# atum-breakout.net
KiCad netlist of a schematic drawn in EAGLE
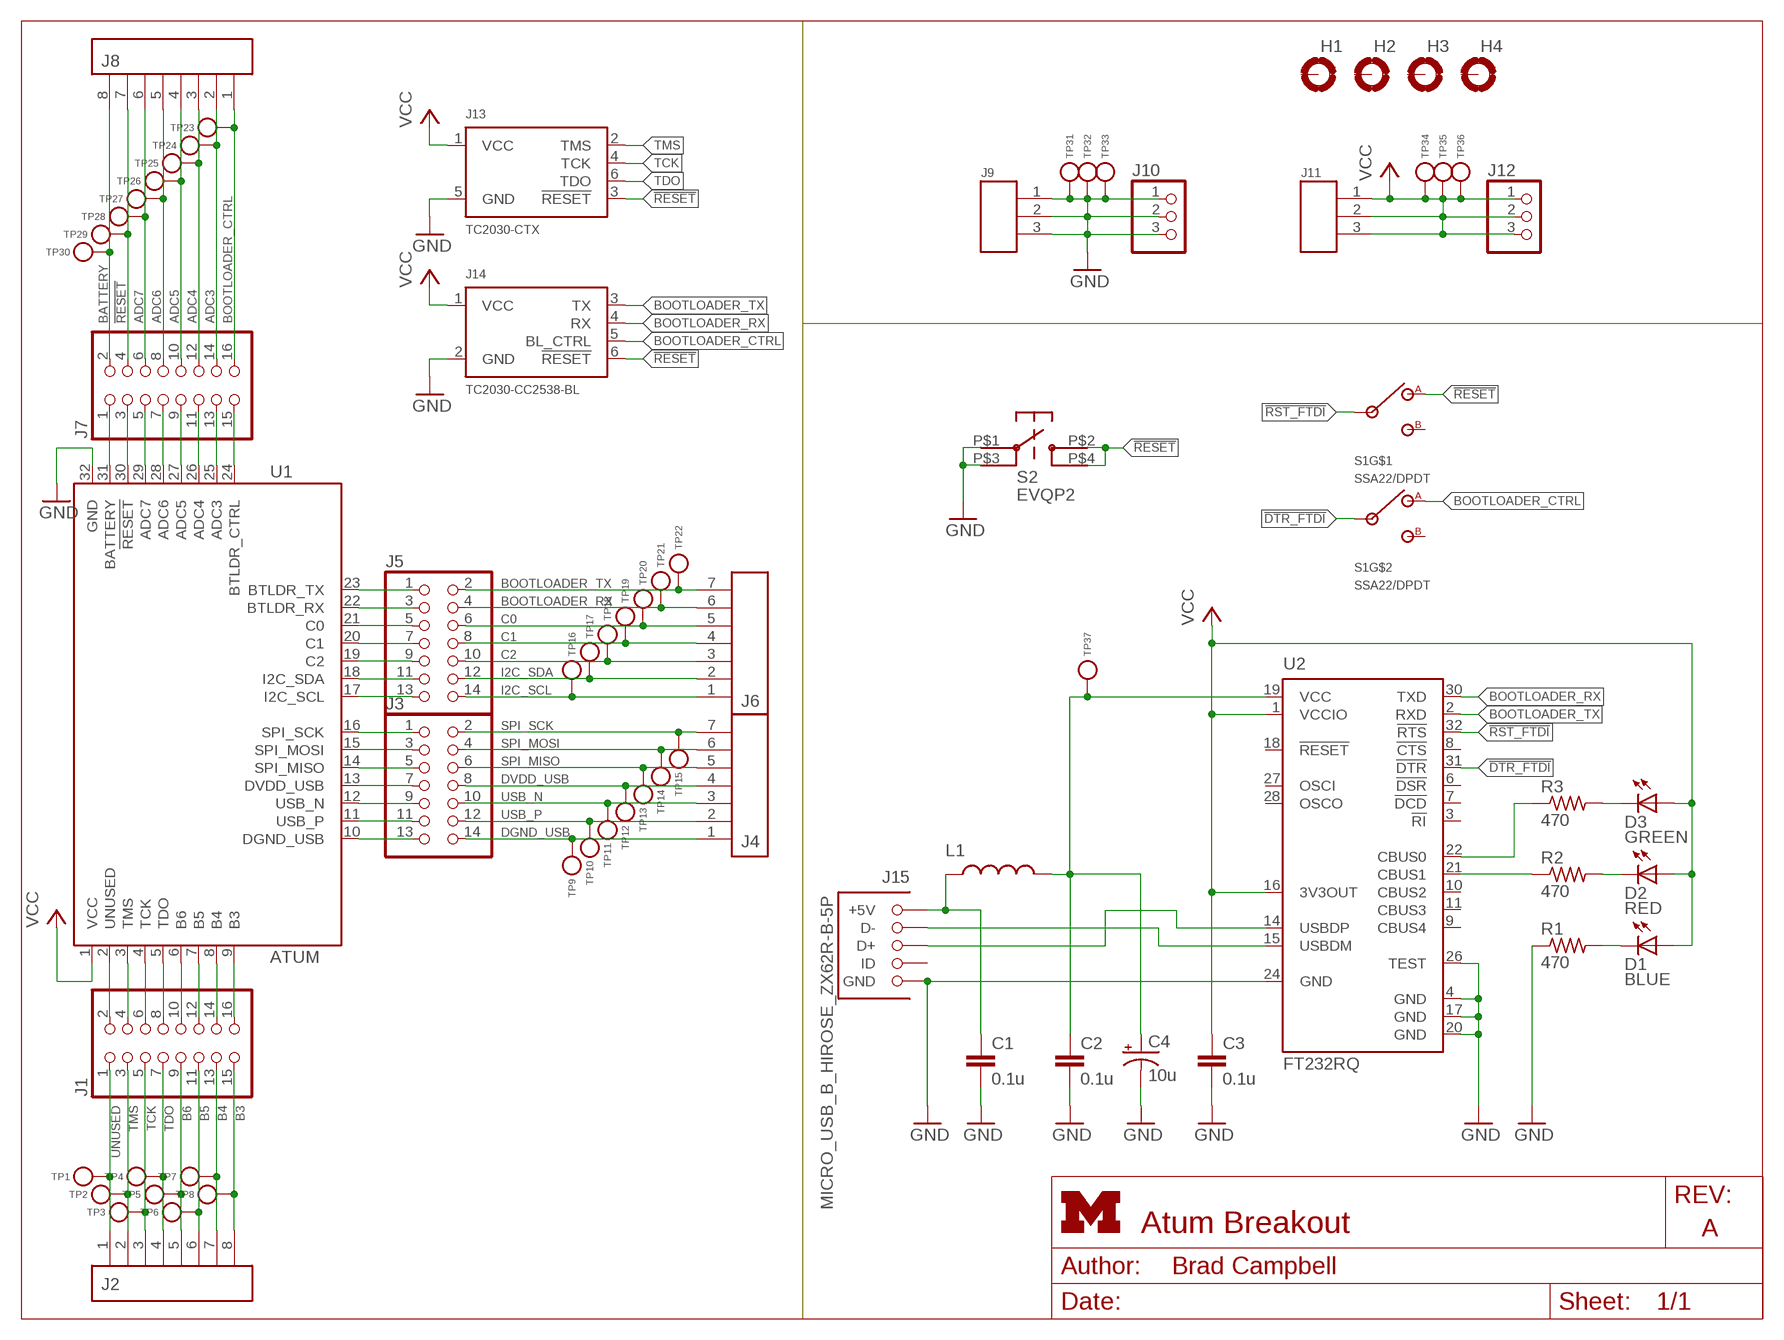
[diagram p0: schematic, sheet 1]

(export (version "E")
  (design (tool "Eeschema 10.0.6"))
  (components
    (comp (ref "C1")
      (value "0.1u")
      (footprint "eagle-import:C0603")
      (libsource (lib "eagle-import") (part "C-EUC0603"))
    )
    (comp (ref "C2")
      (value "0.1u")
      (footprint "eagle-import:C0603")
      (libsource (lib "eagle-import") (part "C-EUC0603"))
    )
    (comp (ref "C3")
      (value "0.1u")
      (footprint "eagle-import:C0603")
      (libsource (lib "eagle-import") (part "C-EUC0603"))
    )
    (comp (ref "C4")
      (value "10u")
      (footprint "eagle-import:EIA3216")
      (libsource (lib "eagle-import") (part "CAP_POL1206"))
    )
    (comp (ref "D1")
      (value "BLUE")
      (footprint "eagle-import:LED-0603")
      (libsource (lib "eagle-import") (part "LED0603"))
    )
    (comp (ref "D2")
      (value "RED")
      (footprint "eagle-import:LED-0603")
      (libsource (lib "eagle-import") (part "LED0603"))
    )
    (comp (ref "D3")
      (value "GREEN")
      (footprint "eagle-import:LED-0603")
      (libsource (lib "eagle-import") (part "LED0603"))
    )
    (comp (ref "H1")
      (value "MOUNT-PAD-ROUND3.2")
      (footprint "eagle-import:3,2-PAD")
      (libsource (lib "eagle-import") (part "MOUNT-PAD-ROUND3.2"))
    )
    (comp (ref "H2")
      (value "MOUNT-PAD-ROUND3.2")
      (footprint "eagle-import:3,2-PAD")
      (libsource (lib "eagle-import") (part "MOUNT-PAD-ROUND3.2"))
    )
    (comp (ref "H3")
      (value "MOUNT-PAD-ROUND3.2")
      (footprint "eagle-import:3,2-PAD")
      (libsource (lib "eagle-import") (part "MOUNT-PAD-ROUND3.2"))
    )
    (comp (ref "H4")
      (value "MOUNT-PAD-ROUND3.2")
      (footprint "eagle-import:3,2-PAD")
      (libsource (lib "eagle-import") (part "MOUNT-PAD-ROUND3.2"))
    )
    (comp (ref "J1")
      (value "PINHD-2X8")
      (footprint "eagle-import:2X08")
      (libsource (lib "eagle-import") (part "PINHD-2X8"))
    )
    (comp (ref "J2")
      (value "SCREW-TERMINAL_8_0.100")
      (footprint "eagle-import:CONN_BLOCK_8")
      (libsource (lib "eagle-import") (part "SCREW-TERMINAL_8_0.100"))
    )
    (comp (ref "J3")
      (value "PINHD-2X7")
      (footprint "eagle-import:2X07")
      (libsource (lib "eagle-import") (part "PINHD-2X7"))
    )
    (comp (ref "J4")
      (value "SCREW-TERMINAL_7_0.100")
      (footprint "eagle-import:CONN_BLOCK_7")
      (libsource (lib "eagle-import") (part "SCREW-TERMINAL_7_0.100"))
    )
    (comp (ref "J5")
      (value "PINHD-2X7")
      (footprint "eagle-import:2X07")
      (libsource (lib "eagle-import") (part "PINHD-2X7"))
    )
    (comp (ref "J6")
      (value "SCREW-TERMINAL_7_0.100")
      (footprint "eagle-import:CONN_BLOCK_7")
      (libsource (lib "eagle-import") (part "SCREW-TERMINAL_7_0.100"))
    )
    (comp (ref "J7")
      (value "PINHD-2X8")
      (footprint "eagle-import:2X08")
      (libsource (lib "eagle-import") (part "PINHD-2X8"))
    )
    (comp (ref "J8")
      (value "SCREW-TERMINAL_8_0.100")
      (footprint "eagle-import:CONN_BLOCK_8")
      (libsource (lib "eagle-import") (part "SCREW-TERMINAL_8_0.100"))
    )
    (comp (ref "J9")
      (value "SCREW-TERMINAL_3_0.100")
      (footprint "eagle-import:CONN_BLOCK_3")
      (libsource (lib "eagle-import") (part "SCREW-TERMINAL_3_0.100"))
    )
    (comp (ref "J10")
      (value "PINHD-1X3")
      (footprint "eagle-import:1X03")
      (libsource (lib "eagle-import") (part "PINHD-1X3"))
    )
    (comp (ref "J11")
      (value "SCREW-TERMINAL_3_0.100")
      (footprint "eagle-import:CONN_BLOCK_3")
      (libsource (lib "eagle-import") (part "SCREW-TERMINAL_3_0.100"))
    )
    (comp (ref "J12")
      (value "PINHD-1X3")
      (footprint "eagle-import:1X03")
      (libsource (lib "eagle-import") (part "PINHD-1X3"))
    )
    (comp (ref "J13")
      (value "TC2030-CTX")
      (footprint "eagle-import:TC2030-IDC")
      (libsource (lib "eagle-import") (part "TC2030-CTX"))
    )
    (comp (ref "J14")
      (value "TC2030-CC2538-BL")
      (footprint "eagle-import:TC2030-IDC")
      (libsource (lib "eagle-import") (part "TC2030-CC2538-BL"))
    )
    (comp (ref "J15")
      (value "MICRO_USB_B_HIROSE_ZX62R-B-5P")
      (footprint "eagle-import:USB_MICRO_B-HIROSE-ZX62R-B-5P")
      (libsource (lib "eagle-import") (part "MICRO_USB_B_HIROSE_ZX62R-B-5P"))
    )
    (comp (ref "L1")
      (value "INDUCTOR0603")
      (footprint "eagle-import:0603")
      (libsource (lib "eagle-import") (part "INDUCTOR0603"))
    )
    (comp (ref "R1")
      (value "470")
      (footprint "eagle-import:R0603")
      (libsource (lib "eagle-import") (part "R-US_R0603"))
    )
    (comp (ref "R2")
      (value "470")
      (footprint "eagle-import:R0603")
      (libsource (lib "eagle-import") (part "R-US_R0603"))
    )
    (comp (ref "R3")
      (value "470")
      (footprint "eagle-import:R0603")
      (libsource (lib "eagle-import") (part "R-US_R0603"))
    )
    (comp (ref "S1")
      (value "SSA22/DPDT")
      (footprint "eagle-import:SSA22_DPDT")
      (fields
        (field (name "DIGIKEY") "450-1604-ND")
        (field (name "MOUSER") "506-SSA22")
        (field (name "NEWARK") "50F5561")
      )
      (libsource (lib "eagle-import") (part "SSA22/DPDT"))
    )
    (comp (ref "S2")
      (value "EVQP2")
      (footprint "eagle-import:EVQP2")
      (libsource (lib "eagle-import") (part "EVQP2"))
    )
    (comp (ref "TP1")
      (value "TEST_POINT_0.040IN")
      (footprint "eagle-import:TESTPOINT_0.040IN")
      (libsource (lib "eagle-import") (part "TEST_POINT_0.040IN"))
    )
    (comp (ref "TP2")
      (value "TEST_POINT_0.040IN")
      (footprint "eagle-import:TESTPOINT_0.040IN")
      (libsource (lib "eagle-import") (part "TEST_POINT_0.040IN"))
    )
    (comp (ref "TP3")
      (value "TEST_POINT_0.040IN")
      (footprint "eagle-import:TESTPOINT_0.040IN")
      (libsource (lib "eagle-import") (part "TEST_POINT_0.040IN"))
    )
    (comp (ref "TP4")
      (value "TEST_POINT_0.040IN")
      (footprint "eagle-import:TESTPOINT_0.040IN")
      (libsource (lib "eagle-import") (part "TEST_POINT_0.040IN"))
    )
    (comp (ref "TP5")
      (value "TEST_POINT_0.040IN")
      (footprint "eagle-import:TESTPOINT_0.040IN")
      (libsource (lib "eagle-import") (part "TEST_POINT_0.040IN"))
    )
    (comp (ref "TP6")
      (value "TEST_POINT_0.040IN")
      (footprint "eagle-import:TESTPOINT_0.040IN")
      (libsource (lib "eagle-import") (part "TEST_POINT_0.040IN"))
    )
    (comp (ref "TP7")
      (value "TEST_POINT_0.040IN")
      (footprint "eagle-import:TESTPOINT_0.040IN")
      (libsource (lib "eagle-import") (part "TEST_POINT_0.040IN"))
    )
    (comp (ref "TP8")
      (value "TEST_POINT_0.040IN")
      (footprint "eagle-import:TESTPOINT_0.040IN")
      (libsource (lib "eagle-import") (part "TEST_POINT_0.040IN"))
    )
    (comp (ref "TP9")
      (value "TEST_POINT_0.040IN")
      (footprint "eagle-import:TESTPOINT_0.040IN")
      (libsource (lib "eagle-import") (part "TEST_POINT_0.040IN"))
    )
    (comp (ref "TP10")
      (value "TEST_POINT_0.040IN")
      (footprint "eagle-import:TESTPOINT_0.040IN")
      (libsource (lib "eagle-import") (part "TEST_POINT_0.040IN"))
    )
    (comp (ref "TP11")
      (value "TEST_POINT_0.040IN")
      (footprint "eagle-import:TESTPOINT_0.040IN")
      (libsource (lib "eagle-import") (part "TEST_POINT_0.040IN"))
    )
    (comp (ref "TP12")
      (value "TEST_POINT_0.040IN")
      (footprint "eagle-import:TESTPOINT_0.040IN")
      (libsource (lib "eagle-import") (part "TEST_POINT_0.040IN"))
    )
    (comp (ref "TP13")
      (value "TEST_POINT_0.040IN")
      (footprint "eagle-import:TESTPOINT_0.040IN")
      (libsource (lib "eagle-import") (part "TEST_POINT_0.040IN"))
    )
    (comp (ref "TP14")
      (value "TEST_POINT_0.040IN")
      (footprint "eagle-import:TESTPOINT_0.040IN")
      (libsource (lib "eagle-import") (part "TEST_POINT_0.040IN"))
    )
    (comp (ref "TP15")
      (value "TEST_POINT_0.040IN")
      (footprint "eagle-import:TESTPOINT_0.040IN")
      (libsource (lib "eagle-import") (part "TEST_POINT_0.040IN"))
    )
    (comp (ref "TP16")
      (value "TEST_POINT_0.040IN")
      (footprint "eagle-import:TESTPOINT_0.040IN")
      (libsource (lib "eagle-import") (part "TEST_POINT_0.040IN"))
    )
    (comp (ref "TP17")
      (value "TEST_POINT_0.040IN")
      (footprint "eagle-import:TESTPOINT_0.040IN")
      (libsource (lib "eagle-import") (part "TEST_POINT_0.040IN"))
    )
    (comp (ref "TP18")
      (value "TEST_POINT_0.040IN")
      (footprint "eagle-import:TESTPOINT_0.040IN")
      (libsource (lib "eagle-import") (part "TEST_POINT_0.040IN"))
    )
    (comp (ref "TP19")
      (value "TEST_POINT_0.040IN")
      (footprint "eagle-import:TESTPOINT_0.040IN")
      (libsource (lib "eagle-import") (part "TEST_POINT_0.040IN"))
    )
    (comp (ref "TP20")
      (value "TEST_POINT_0.040IN")
      (footprint "eagle-import:TESTPOINT_0.040IN")
      (libsource (lib "eagle-import") (part "TEST_POINT_0.040IN"))
    )
    (comp (ref "TP21")
      (value "TEST_POINT_0.040IN")
      (footprint "eagle-import:TESTPOINT_0.040IN")
      (libsource (lib "eagle-import") (part "TEST_POINT_0.040IN"))
    )
    (comp (ref "TP22")
      (value "TEST_POINT_0.040IN")
      (footprint "eagle-import:TESTPOINT_0.040IN")
      (libsource (lib "eagle-import") (part "TEST_POINT_0.040IN"))
    )
    (comp (ref "TP23")
      (value "TEST_POINT_0.040IN")
      (footprint "eagle-import:TESTPOINT_0.040IN")
      (libsource (lib "eagle-import") (part "TEST_POINT_0.040IN"))
    )
    (comp (ref "TP24")
      (value "TEST_POINT_0.040IN")
      (footprint "eagle-import:TESTPOINT_0.040IN")
      (libsource (lib "eagle-import") (part "TEST_POINT_0.040IN"))
    )
    (comp (ref "TP25")
      (value "TEST_POINT_0.040IN")
      (footprint "eagle-import:TESTPOINT_0.040IN")
      (libsource (lib "eagle-import") (part "TEST_POINT_0.040IN"))
    )
    (comp (ref "TP26")
      (value "TEST_POINT_0.040IN")
      (footprint "eagle-import:TESTPOINT_0.040IN")
      (libsource (lib "eagle-import") (part "TEST_POINT_0.040IN"))
    )
    (comp (ref "TP27")
      (value "TEST_POINT_0.040IN")
      (footprint "eagle-import:TESTPOINT_0.040IN")
      (libsource (lib "eagle-import") (part "TEST_POINT_0.040IN"))
    )
    (comp (ref "TP28")
      (value "TEST_POINT_0.040IN")
      (footprint "eagle-import:TESTPOINT_0.040IN")
      (libsource (lib "eagle-import") (part "TEST_POINT_0.040IN"))
    )
    (comp (ref "TP29")
      (value "TEST_POINT_0.040IN")
      (footprint "eagle-import:TESTPOINT_0.040IN")
      (libsource (lib "eagle-import") (part "TEST_POINT_0.040IN"))
    )
    (comp (ref "TP30")
      (value "TEST_POINT_0.040IN")
      (footprint "eagle-import:TESTPOINT_0.040IN")
      (libsource (lib "eagle-import") (part "TEST_POINT_0.040IN"))
    )
    (comp (ref "TP31")
      (value "TEST_POINT_0.040IN")
      (footprint "eagle-import:TESTPOINT_0.040IN")
      (libsource (lib "eagle-import") (part "TEST_POINT_0.040IN"))
    )
    (comp (ref "TP32")
      (value "TEST_POINT_0.040IN")
      (footprint "eagle-import:TESTPOINT_0.040IN")
      (libsource (lib "eagle-import") (part "TEST_POINT_0.040IN"))
    )
    (comp (ref "TP33")
      (value "TEST_POINT_0.040IN")
      (footprint "eagle-import:TESTPOINT_0.040IN")
      (libsource (lib "eagle-import") (part "TEST_POINT_0.040IN"))
    )
    (comp (ref "TP34")
      (value "TEST_POINT_0.040IN")
      (footprint "eagle-import:TESTPOINT_0.040IN")
      (libsource (lib "eagle-import") (part "TEST_POINT_0.040IN"))
    )
    (comp (ref "TP35")
      (value "TEST_POINT_0.040IN")
      (footprint "eagle-import:TESTPOINT_0.040IN")
      (libsource (lib "eagle-import") (part "TEST_POINT_0.040IN"))
    )
    (comp (ref "TP36")
      (value "TEST_POINT_0.040IN")
      (footprint "eagle-import:TESTPOINT_0.040IN")
      (libsource (lib "eagle-import") (part "TEST_POINT_0.040IN"))
    )
    (comp (ref "TP37")
      (value "TEST_POINT_0.040IN")
      (footprint "eagle-import:TESTPOINT_0.040IN")
      (libsource (lib "eagle-import") (part "TEST_POINT_0.040IN"))
    )
    (comp (ref "U1")
      (value "ATUM")
      (footprint "eagle-import:ATUM")
      (libsource (lib "eagle-import") (part "ATUM"))
    )
    (comp (ref "U2")
      (value "FT232RQ")
      (footprint "eagle-import:QFN32")
      (libsource (lib "eagle-import") (part "FT232RQ"))
    )
  )
  (nets
    (net (code "1") (name "/ADC3") (class "Default")
      (node (ref "J7") (pin "13") (pinfunction "13_13") (pintype "passive"))
      (node (ref "J7") (pin "14") (pinfunction "14_14") (pintype "passive"))
      (node (ref "J8") (pin "2") (pinfunction "2_2") (pintype "bidirectional"))
      (node (ref "TP24") (pin "TESTPOINT") (pinfunction "TESTPOINT_TESTPOINT") (pintype "bidirectional"))
      (node (ref "U1") (pin "25") (pinfunction "ADC3_25") (pintype "bidirectional"))
    )
    (net (code "2") (name "/ADC4") (class "Default")
      (node (ref "J7") (pin "11") (pinfunction "11_11") (pintype "passive"))
      (node (ref "J7") (pin "12") (pinfunction "12_12") (pintype "passive"))
      (node (ref "J8") (pin "3") (pinfunction "3_3") (pintype "bidirectional"))
      (node (ref "TP25") (pin "TESTPOINT") (pinfunction "TESTPOINT_TESTPOINT") (pintype "bidirectional"))
      (node (ref "U1") (pin "26") (pinfunction "ADC4_26") (pintype "bidirectional"))
    )
    (net (code "3") (name "/ADC5") (class "Default")
      (node (ref "J7") (pin "10") (pinfunction "10_10") (pintype "passive"))
      (node (ref "J7") (pin "9") (pinfunction "9_9") (pintype "passive"))
      (node (ref "J8") (pin "4") (pinfunction "4_4") (pintype "bidirectional"))
      (node (ref "TP26") (pin "TESTPOINT") (pinfunction "TESTPOINT_TESTPOINT") (pintype "bidirectional"))
      (node (ref "U1") (pin "27") (pinfunction "ADC5_27") (pintype "bidirectional"))
    )
    (net (code "4") (name "/ADC6") (class "Default")
      (node (ref "J7") (pin "7") (pinfunction "7_7") (pintype "passive"))
      (node (ref "J7") (pin "8") (pinfunction "8_8") (pintype "passive"))
      (node (ref "J8") (pin "5") (pinfunction "5_5") (pintype "bidirectional"))
      (node (ref "TP27") (pin "TESTPOINT") (pinfunction "TESTPOINT_TESTPOINT") (pintype "bidirectional"))
      (node (ref "U1") (pin "28") (pinfunction "ADC6_28") (pintype "bidirectional"))
    )
    (net (code "5") (name "/ADC7") (class "Default")
      (node (ref "J7") (pin "5") (pinfunction "5_5") (pintype "passive"))
      (node (ref "J7") (pin "6") (pinfunction "6_6") (pintype "passive"))
      (node (ref "J8") (pin "6") (pinfunction "6_6") (pintype "bidirectional"))
      (node (ref "TP28") (pin "TESTPOINT") (pinfunction "TESTPOINT_TESTPOINT") (pintype "bidirectional"))
      (node (ref "U1") (pin "29") (pinfunction "ADC7_29") (pintype "bidirectional"))
    )
    (net (code "6") (name "/B3") (class "Default")
      (node (ref "J1") (pin "15") (pinfunction "15_15") (pintype "passive"))
      (node (ref "J1") (pin "16") (pinfunction "16_16") (pintype "passive"))
      (node (ref "J2") (pin "8") (pinfunction "8_8") (pintype "bidirectional"))
      (node (ref "TP8") (pin "TESTPOINT") (pinfunction "TESTPOINT_TESTPOINT") (pintype "bidirectional"))
      (node (ref "U1") (pin "9") (pinfunction "B3_9") (pintype "bidirectional"))
    )
    (net (code "7") (name "/B4") (class "Default")
      (node (ref "J1") (pin "13") (pinfunction "13_13") (pintype "passive"))
      (node (ref "J1") (pin "14") (pinfunction "14_14") (pintype "passive"))
      (node (ref "J2") (pin "7") (pinfunction "7_7") (pintype "bidirectional"))
      (node (ref "TP7") (pin "TESTPOINT") (pinfunction "TESTPOINT_TESTPOINT") (pintype "bidirectional"))
      (node (ref "U1") (pin "8") (pinfunction "B4_8") (pintype "bidirectional"))
    )
    (net (code "8") (name "/B5") (class "Default")
      (node (ref "J1") (pin "11") (pinfunction "11_11") (pintype "passive"))
      (node (ref "J1") (pin "12") (pinfunction "12_12") (pintype "passive"))
      (node (ref "J2") (pin "6") (pinfunction "6_6") (pintype "bidirectional"))
      (node (ref "TP6") (pin "TESTPOINT") (pinfunction "TESTPOINT_TESTPOINT") (pintype "bidirectional"))
      (node (ref "U1") (pin "7") (pinfunction "B5_7") (pintype "bidirectional"))
    )
    (net (code "9") (name "/B6") (class "Default")
      (node (ref "J1") (pin "10") (pinfunction "10_10") (pintype "passive"))
      (node (ref "J1") (pin "9") (pinfunction "9_9") (pintype "passive"))
      (node (ref "J2") (pin "5") (pinfunction "5_5") (pintype "bidirectional"))
      (node (ref "TP5") (pin "TESTPOINT") (pinfunction "TESTPOINT_TESTPOINT") (pintype "bidirectional"))
      (node (ref "U1") (pin "6") (pinfunction "B6_6") (pintype "bidirectional"))
    )
    (net (code "10") (name "/BATTERY") (class "Default")
      (node (ref "J7") (pin "1") (pinfunction "1_1") (pintype "passive"))
      (node (ref "J7") (pin "2") (pinfunction "2_2") (pintype "passive"))
      (node (ref "J8") (pin "8") (pinfunction "8_8") (pintype "bidirectional"))
      (node (ref "TP30") (pin "TESTPOINT") (pinfunction "TESTPOINT_TESTPOINT") (pintype "bidirectional"))
      (node (ref "U1") (pin "31") (pinfunction "BATTERY_31") (pintype "bidirectional"))
    )
    (net (code "11") (name "/C0") (class "Default")
      (node (ref "J5") (pin "5") (pinfunction "5_5") (pintype "passive"))
      (node (ref "J5") (pin "6") (pinfunction "6_6") (pintype "passive"))
      (node (ref "J6") (pin "5") (pinfunction "5_5") (pintype "bidirectional"))
      (node (ref "TP20") (pin "TESTPOINT") (pinfunction "TESTPOINT_TESTPOINT") (pintype "bidirectional"))
      (node (ref "U1") (pin "21") (pinfunction "C0_21") (pintype "bidirectional"))
    )
    (net (code "12") (name "/C1") (class "Default")
      (node (ref "J5") (pin "7") (pinfunction "7_7") (pintype "passive"))
      (node (ref "J5") (pin "8") (pinfunction "8_8") (pintype "passive"))
      (node (ref "J6") (pin "4") (pinfunction "4_4") (pintype "bidirectional"))
      (node (ref "TP19") (pin "TESTPOINT") (pinfunction "TESTPOINT_TESTPOINT") (pintype "bidirectional"))
      (node (ref "U1") (pin "20") (pinfunction "C1_20") (pintype "bidirectional"))
    )
    (net (code "13") (name "/C2") (class "Default")
      (node (ref "J5") (pin "10") (pinfunction "10_10") (pintype "passive"))
      (node (ref "J5") (pin "9") (pinfunction "9_9") (pintype "passive"))
      (node (ref "J6") (pin "3") (pinfunction "3_3") (pintype "bidirectional"))
      (node (ref "TP18") (pin "TESTPOINT") (pinfunction "TESTPOINT_TESTPOINT") (pintype "bidirectional"))
      (node (ref "U1") (pin "19") (pinfunction "C2_19") (pintype "bidirectional"))
    )
    (net (code "14") (name "/DGND_USB") (class "Default")
      (node (ref "J3") (pin "13") (pinfunction "13_13") (pintype "passive"))
      (node (ref "J3") (pin "14") (pinfunction "14_14") (pintype "passive"))
      (node (ref "J4") (pin "1") (pinfunction "1_1") (pintype "bidirectional"))
      (node (ref "TP9") (pin "TESTPOINT") (pinfunction "TESTPOINT_TESTPOINT") (pintype "bidirectional"))
      (node (ref "U1") (pin "10") (pinfunction "DGND_USB_10") (pintype "bidirectional"))
    )
    (net (code "15") (name "/DVDD_USB") (class "Default")
      (node (ref "J3") (pin "7") (pinfunction "7_7") (pintype "passive"))
      (node (ref "J3") (pin "8") (pinfunction "8_8") (pintype "passive"))
      (node (ref "J4") (pin "4") (pinfunction "4_4") (pintype "bidirectional"))
      (node (ref "TP12") (pin "TESTPOINT") (pinfunction "TESTPOINT_TESTPOINT") (pintype "bidirectional"))
      (node (ref "U1") (pin "13") (pinfunction "DVDD_USB_13") (pintype "bidirectional"))
    )
    (net (code "16") (name "/I2C_SCL") (class "Default")
      (node (ref "J5") (pin "13") (pinfunction "13_13") (pintype "passive"))
      (node (ref "J5") (pin "14") (pinfunction "14_14") (pintype "passive"))
      (node (ref "J6") (pin "1") (pinfunction "1_1") (pintype "bidirectional"))
      (node (ref "TP16") (pin "TESTPOINT") (pinfunction "TESTPOINT_TESTPOINT") (pintype "bidirectional"))
      (node (ref "U1") (pin "17") (pinfunction "I2C_SCL_17") (pintype "bidirectional"))
    )
    (net (code "17") (name "/I2C_SDA") (class "Default")
      (node (ref "J5") (pin "11") (pinfunction "11_11") (pintype "passive"))
      (node (ref "J5") (pin "12") (pinfunction "12_12") (pintype "passive"))
      (node (ref "J6") (pin "2") (pinfunction "2_2") (pintype "bidirectional"))
      (node (ref "TP17") (pin "TESTPOINT") (pinfunction "TESTPOINT_TESTPOINT") (pintype "bidirectional"))
      (node (ref "U1") (pin "18") (pinfunction "I2C_SDA_18") (pintype "bidirectional"))
    )
    (net (code "18") (name "/SPI_MISO") (class "Default")
      (node (ref "J3") (pin "5") (pinfunction "5_5") (pintype "passive"))
      (node (ref "J3") (pin "6") (pinfunction "6_6") (pintype "passive"))
      (node (ref "J4") (pin "5") (pinfunction "5_5") (pintype "bidirectional"))
      (node (ref "TP13") (pin "TESTPOINT") (pinfunction "TESTPOINT_TESTPOINT") (pintype "bidirectional"))
      (node (ref "U1") (pin "14") (pinfunction "SPI_MISO_14") (pintype "bidirectional"))
    )
    (net (code "19") (name "/SPI_MOSI") (class "Default")
      (node (ref "J3") (pin "3") (pinfunction "3_3") (pintype "passive"))
      (node (ref "J3") (pin "4") (pinfunction "4_4") (pintype "passive"))
      (node (ref "J4") (pin "6") (pinfunction "6_6") (pintype "bidirectional"))
      (node (ref "TP14") (pin "TESTPOINT") (pinfunction "TESTPOINT_TESTPOINT") (pintype "bidirectional"))
      (node (ref "U1") (pin "15") (pinfunction "SPI_MOSI_15") (pintype "bidirectional"))
    )
    (net (code "20") (name "/SPI_SCK") (class "Default")
      (node (ref "J3") (pin "1") (pinfunction "1_1") (pintype "passive"))
      (node (ref "J3") (pin "2") (pinfunction "2_2") (pintype "passive"))
      (node (ref "J4") (pin "7") (pinfunction "7_7") (pintype "bidirectional"))
      (node (ref "TP15") (pin "TESTPOINT") (pinfunction "TESTPOINT_TESTPOINT") (pintype "bidirectional"))
      (node (ref "U1") (pin "16") (pinfunction "SPI_SCK_16") (pintype "bidirectional"))
    )
    (net (code "21") (name "/UNUSED") (class "Default")
      (node (ref "J1") (pin "1") (pinfunction "1_1") (pintype "passive"))
      (node (ref "J1") (pin "2") (pinfunction "2_2") (pintype "passive"))
      (node (ref "J2") (pin "1") (pinfunction "1_1") (pintype "bidirectional"))
      (node (ref "TP1") (pin "TESTPOINT") (pinfunction "TESTPOINT_TESTPOINT") (pintype "bidirectional"))
      (node (ref "U1") (pin "2") (pinfunction "UNUSED_2") (pintype "bidirectional"))
    )
    (net (code "22") (name "/USB_N") (class "Default")
      (node (ref "J3") (pin "10") (pinfunction "10_10") (pintype "passive"))
      (node (ref "J3") (pin "9") (pinfunction "9_9") (pintype "passive"))
      (node (ref "J4") (pin "3") (pinfunction "3_3") (pintype "bidirectional"))
      (node (ref "TP11") (pin "TESTPOINT") (pinfunction "TESTPOINT_TESTPOINT") (pintype "bidirectional"))
      (node (ref "U1") (pin "12") (pinfunction "USB_N_12") (pintype "bidirectional"))
    )
    (net (code "23") (name "/USB_P") (class "Default")
      (node (ref "J3") (pin "11") (pinfunction "11_11") (pintype "passive"))
      (node (ref "J3") (pin "12") (pinfunction "12_12") (pintype "passive"))
      (node (ref "J4") (pin "2") (pinfunction "2_2") (pintype "bidirectional"))
      (node (ref "TP10") (pin "TESTPOINT") (pinfunction "TESTPOINT_TESTPOINT") (pintype "bidirectional"))
      (node (ref "U1") (pin "11") (pinfunction "USB_P_11") (pintype "bidirectional"))
    )
    (net (code "24") (name "/~{DTR_FTDI}") (class "Default")
      (node (ref "S1") (pin "COM2") (pinfunction "2_COM2") (pintype "bidirectional"))
      (node (ref "U2") (pin "31") (pinfunction "~{DTR}_31") (pintype "output"))
    )
    (net (code "25") (name "/~{RESET}") (class "Default")
      (node (ref "J13") (pin "3") (pinfunction "~{RESET}_3") (pintype "bidirectional"))
      (node (ref "J14") (pin "6") (pinfunction "~{RESET}_6") (pintype "bidirectional"))
      (node (ref "J7") (pin "3") (pinfunction "3_3") (pintype "passive"))
      (node (ref "J7") (pin "4") (pinfunction "4_4") (pintype "passive"))
      (node (ref "J8") (pin "7") (pinfunction "7_7") (pintype "bidirectional"))
      (node (ref "S1") (pin "A1") (pinfunction "1_A1") (pintype "bidirectional"))
      (node (ref "S2") (pin "P$2") (pinfunction "P$2_P$2") (pintype "passive"))
      (node (ref "S2") (pin "P$4") (pinfunction "P$4_P$4") (pintype "passive"))
      (node (ref "TP29") (pin "TESTPOINT") (pinfunction "TESTPOINT_TESTPOINT") (pintype "bidirectional"))
      (node (ref "U1") (pin "30") (pinfunction "~{RESET}_30") (pintype "bidirectional"))
    )
    (net (code "26") (name "/~{RST_FTDI}") (class "Default")
      (node (ref "S1") (pin "COM1") (pinfunction "2_COM1") (pintype "bidirectional"))
      (node (ref "U2") (pin "32") (pinfunction "~{RTS}_32") (pintype "output"))
    )
    (net (code "27") (name "BOOTLOADER_CTRL") (class "Default")
      (node (ref "J14") (pin "5") (pinfunction "BL_CTRL_5") (pintype "bidirectional"))
      (node (ref "J7") (pin "15") (pinfunction "15_15") (pintype "passive"))
      (node (ref "J7") (pin "16") (pinfunction "16_16") (pintype "passive"))
      (node (ref "J8") (pin "1") (pinfunction "1_1") (pintype "bidirectional"))
      (node (ref "S1") (pin "A2") (pinfunction "1_A2") (pintype "bidirectional"))
      (node (ref "TP23") (pin "TESTPOINT") (pinfunction "TESTPOINT_TESTPOINT") (pintype "bidirectional"))
      (node (ref "U1") (pin "24") (pinfunction "BTLDR_CTRL_24") (pintype "bidirectional"))
    )
    (net (code "28") (name "BOOTLOADER_RX") (class "Default")
      (node (ref "J14") (pin "4") (pinfunction "RX_4") (pintype "bidirectional"))
      (node (ref "J5") (pin "3") (pinfunction "3_3") (pintype "passive"))
      (node (ref "J5") (pin "4") (pinfunction "4_4") (pintype "passive"))
      (node (ref "J6") (pin "6") (pinfunction "6_6") (pintype "bidirectional"))
      (node (ref "TP21") (pin "TESTPOINT") (pinfunction "TESTPOINT_TESTPOINT") (pintype "bidirectional"))
      (node (ref "U1") (pin "22") (pinfunction "BTLDR_RX_22") (pintype "bidirectional"))
      (node (ref "U2") (pin "30") (pinfunction "TXD_30") (pintype "output"))
    )
    (net (code "29") (name "BOOTLOADER_TX") (class "Default")
      (node (ref "J14") (pin "3") (pinfunction "TX_3") (pintype "bidirectional"))
      (node (ref "J5") (pin "1") (pinfunction "1_1") (pintype "passive"))
      (node (ref "J5") (pin "2") (pinfunction "2_2") (pintype "passive"))
      (node (ref "J6") (pin "7") (pinfunction "7_7") (pintype "bidirectional"))
      (node (ref "TP22") (pin "TESTPOINT") (pinfunction "TESTPOINT_TESTPOINT") (pintype "bidirectional"))
      (node (ref "U1") (pin "23") (pinfunction "BTLDR_TX_23") (pintype "bidirectional"))
      (node (ref "U2") (pin "2") (pinfunction "RXD_2") (pintype "input"))
    )
    (net (code "30") (name "GND") (class "Default")
      (node (ref "C1") (pin "2") (pinfunction "2_2") (pintype "passive"))
      (node (ref "C2") (pin "2") (pinfunction "2_2") (pintype "passive"))
      (node (ref "C3") (pin "2") (pinfunction "2_2") (pintype "passive"))
      (node (ref "C4") (pin "C") (pinfunction "-_C") (pintype "passive"))
      (node (ref "J10") (pin "1") (pinfunction "1_1") (pintype "passive"))
      (node (ref "J10") (pin "2") (pinfunction "2_2") (pintype "passive"))
      (node (ref "J10") (pin "3") (pinfunction "3_3") (pintype "passive"))
      (node (ref "J13") (pin "5") (pinfunction "GND_5") (pintype "bidirectional"))
      (node (ref "J14") (pin "2") (pinfunction "GND_2") (pintype "bidirectional"))
      (node (ref "J15") (pin "5") (pinfunction "GND_5") (pintype "bidirectional"))
      (node (ref "J9") (pin "1") (pinfunction "1_1") (pintype "bidirectional"))
      (node (ref "J9") (pin "2") (pinfunction "2_2") (pintype "bidirectional"))
      (node (ref "J9") (pin "3") (pinfunction "3_3") (pintype "bidirectional"))
      (node (ref "R1") (pin "1") (pinfunction "1_1") (pintype "passive"))
      (node (ref "S2") (pin "P$1") (pinfunction "P$1_P$1") (pintype "passive"))
      (node (ref "S2") (pin "P$3") (pinfunction "P$3_P$3") (pintype "passive"))
      (node (ref "TP31") (pin "TESTPOINT") (pinfunction "TESTPOINT_TESTPOINT") (pintype "bidirectional"))
      (node (ref "TP32") (pin "TESTPOINT") (pinfunction "TESTPOINT_TESTPOINT") (pintype "bidirectional"))
      (node (ref "TP33") (pin "TESTPOINT") (pinfunction "TESTPOINT_TESTPOINT") (pintype "bidirectional"))
      (node (ref "U1") (pin "32") (pinfunction "GND_32") (pintype "bidirectional"))
      (node (ref "U2") (pin "17") (pinfunction "GND_17") (pintype "power_in"))
      (node (ref "U2") (pin "20") (pinfunction "GND_20") (pintype "power_in"))
      (node (ref "U2") (pin "24") (pinfunction "GND_24") (pintype "power_in"))
      (node (ref "U2") (pin "26") (pinfunction "TEST_26") (pintype "input"))
      (node (ref "U2") (pin "4") (pinfunction "GND_4") (pintype "power_in"))
    )
    (net (code "31") (name "Net-(C4-+)") (class "Default")
      (node (ref "C2") (pin "1") (pinfunction "1_1") (pintype "passive"))
      (node (ref "C4") (pin "A") (pinfunction "+_A") (pintype "passive"))
      (node (ref "L1") (pin "2") (pinfunction "2_2") (pintype "passive"))
      (node (ref "TP37") (pin "TESTPOINT") (pinfunction "TESTPOINT_TESTPOINT") (pintype "bidirectional"))
      (node (ref "U2") (pin "19") (pinfunction "VCC_19") (pintype "power_in"))
    )
    (net (code "32") (name "Net-(D1-PadC)") (class "Default")
      (node (ref "D1") (pin "C") (pinfunction "C_C") (pintype "passive"))
      (node (ref "R1") (pin "2") (pinfunction "2_2") (pintype "passive"))
    )
    (net (code "33") (name "Net-(D2-PadC)") (class "Default")
      (node (ref "D2") (pin "C") (pinfunction "C_C") (pintype "passive"))
      (node (ref "R2") (pin "2") (pinfunction "2_2") (pintype "passive"))
    )
    (net (code "34") (name "Net-(D3-PadC)") (class "Default")
      (node (ref "D3") (pin "C") (pinfunction "C_C") (pintype "passive"))
      (node (ref "R3") (pin "2") (pinfunction "2_2") (pintype "passive"))
    )
    (net (code "35") (name "Net-(J15-+5V)") (class "Default")
      (node (ref "C1") (pin "1") (pinfunction "1_1") (pintype "passive"))
      (node (ref "J15") (pin "1") (pinfunction "+5V_1") (pintype "bidirectional"))
      (node (ref "L1") (pin "1") (pinfunction "1_1") (pintype "passive"))
    )
    (net (code "36") (name "Net-(J15-D+)") (class "Default")
      (node (ref "J15") (pin "3") (pinfunction "D+_3") (pintype "bidirectional"))
      (node (ref "U2") (pin "14") (pinfunction "USBDP_14") (pintype "bidirectional"))
    )
    (net (code "37") (name "Net-(J15-D-)") (class "Default")
      (node (ref "J15") (pin "2") (pinfunction "D-_2") (pintype "bidirectional"))
      (node (ref "U2") (pin "15") (pinfunction "USBDM_15") (pintype "bidirectional"))
    )
    (net (code "38") (name "Net-(U2-CBUS0)") (class "Default")
      (node (ref "R3") (pin "1") (pinfunction "1_1") (pintype "passive"))
      (node (ref "U2") (pin "22") (pinfunction "CBUS0_22") (pintype "bidirectional"))
    )
    (net (code "39") (name "Net-(U2-CBUS1)") (class "Default")
      (node (ref "R2") (pin "1") (pinfunction "1_1") (pintype "passive"))
      (node (ref "U2") (pin "21") (pinfunction "CBUS1_21") (pintype "bidirectional"))
    )
    (net (code "40") (name "TCK") (class "Default")
      (node (ref "J1") (pin "5") (pinfunction "5_5") (pintype "passive"))
      (node (ref "J1") (pin "6") (pinfunction "6_6") (pintype "passive"))
      (node (ref "J13") (pin "4") (pinfunction "TCK_4") (pintype "bidirectional"))
      (node (ref "J2") (pin "3") (pinfunction "3_3") (pintype "bidirectional"))
      (node (ref "TP3") (pin "TESTPOINT") (pinfunction "TESTPOINT_TESTPOINT") (pintype "bidirectional"))
      (node (ref "U1") (pin "4") (pinfunction "TCK_4") (pintype "bidirectional"))
    )
    (net (code "41") (name "TDO") (class "Default")
      (node (ref "J1") (pin "7") (pinfunction "7_7") (pintype "passive"))
      (node (ref "J1") (pin "8") (pinfunction "8_8") (pintype "passive"))
      (node (ref "J13") (pin "6") (pinfunction "TDO_6") (pintype "bidirectional"))
      (node (ref "J2") (pin "4") (pinfunction "4_4") (pintype "bidirectional"))
      (node (ref "TP4") (pin "TESTPOINT") (pinfunction "TESTPOINT_TESTPOINT") (pintype "bidirectional"))
      (node (ref "U1") (pin "5") (pinfunction "TDO_5") (pintype "bidirectional"))
    )
    (net (code "42") (name "TMS") (class "Default")
      (node (ref "J1") (pin "3") (pinfunction "3_3") (pintype "passive"))
      (node (ref "J1") (pin "4") (pinfunction "4_4") (pintype "passive"))
      (node (ref "J13") (pin "2") (pinfunction "TMS_2") (pintype "bidirectional"))
      (node (ref "J2") (pin "2") (pinfunction "2_2") (pintype "bidirectional"))
      (node (ref "TP2") (pin "TESTPOINT") (pinfunction "TESTPOINT_TESTPOINT") (pintype "bidirectional"))
      (node (ref "U1") (pin "3") (pinfunction "TMS_3") (pintype "bidirectional"))
    )
    (net (code "43") (name "VCC") (class "Default")
      (node (ref "C3") (pin "1") (pinfunction "1_1") (pintype "passive"))
      (node (ref "D1") (pin "A") (pinfunction "A_A") (pintype "passive"))
      (node (ref "D2") (pin "A") (pinfunction "A_A") (pintype "passive"))
      (node (ref "D3") (pin "A") (pinfunction "A_A") (pintype "passive"))
      (node (ref "J11") (pin "1") (pinfunction "1_1") (pintype "bidirectional"))
      (node (ref "J11") (pin "2") (pinfunction "2_2") (pintype "bidirectional"))
      (node (ref "J11") (pin "3") (pinfunction "3_3") (pintype "bidirectional"))
      (node (ref "J12") (pin "1") (pinfunction "1_1") (pintype "passive"))
      (node (ref "J12") (pin "2") (pinfunction "2_2") (pintype "passive"))
      (node (ref "J12") (pin "3") (pinfunction "3_3") (pintype "passive"))
      (node (ref "J13") (pin "1") (pinfunction "VCC_1") (pintype "bidirectional"))
      (node (ref "J14") (pin "1") (pinfunction "VCC_1") (pintype "bidirectional"))
      (node (ref "TP34") (pin "TESTPOINT") (pinfunction "TESTPOINT_TESTPOINT") (pintype "bidirectional"))
      (node (ref "TP35") (pin "TESTPOINT") (pinfunction "TESTPOINT_TESTPOINT") (pintype "bidirectional"))
      (node (ref "TP36") (pin "TESTPOINT") (pinfunction "TESTPOINT_TESTPOINT") (pintype "bidirectional"))
      (node (ref "U1") (pin "1") (pinfunction "VCC_1") (pintype "bidirectional"))
      (node (ref "U2") (pin "1") (pinfunction "VCCIO_1") (pintype "power_in"))
      (node (ref "U2") (pin "16") (pinfunction "3V3OUT_16") (pintype "output"))
    )
    (net (code "44") (name "unconnected-(H1-MOUNT-PadB3,2)") (class "Default")
      (node (ref "H1") (pin "B3,2") (pinfunction "MOUNT_B3,2") (pintype "passive"))
    )
    (net (code "45") (name "unconnected-(H2-MOUNT-PadB3,2)") (class "Default")
      (node (ref "H2") (pin "B3,2") (pinfunction "MOUNT_B3,2") (pintype "passive"))
    )
    (net (code "46") (name "unconnected-(H3-MOUNT-PadB3,2)") (class "Default")
      (node (ref "H3") (pin "B3,2") (pinfunction "MOUNT_B3,2") (pintype "passive"))
    )
    (net (code "47") (name "unconnected-(H4-MOUNT-PadB3,2)") (class "Default")
      (node (ref "H4") (pin "B3,2") (pinfunction "MOUNT_B3,2") (pintype "passive"))
    )
    (net (code "48") (name "unconnected-(J15-ID-Pad4)") (class "Default")
      (node (ref "J15") (pin "4") (pinfunction "ID_4") (pintype "bidirectional"))
    )
    (net (code "49") (name "unconnected-(S1A-3-PadB1)") (class "Default")
      (node (ref "S1") (pin "B1") (pinfunction "3_B1") (pintype "bidirectional"))
    )
    (net (code "50") (name "unconnected-(S1B-3-PadB2)") (class "Default")
      (node (ref "S1") (pin "B2") (pinfunction "3_B2") (pintype "bidirectional"))
    )
    (net (code "51") (name "unconnected-(U2-CBUS2-Pad10)") (class "Default")
      (node (ref "U2") (pin "10") (pinfunction "CBUS2_10") (pintype "bidirectional"))
    )
    (net (code "52") (name "unconnected-(U2-CBUS3-Pad11)") (class "Default")
      (node (ref "U2") (pin "11") (pinfunction "CBUS3_11") (pintype "bidirectional"))
    )
    (net (code "53") (name "unconnected-(U2-CBUS4-Pad9)") (class "Default")
      (node (ref "U2") (pin "9") (pinfunction "CBUS4_9") (pintype "bidirectional"))
    )
    (net (code "54") (name "unconnected-(U2-OSCI-Pad27)") (class "Default")
      (node (ref "U2") (pin "27") (pinfunction "OSCI_27") (pintype "input"))
    )
    (net (code "55") (name "unconnected-(U2-OSCO-Pad28)") (class "Default")
      (node (ref "U2") (pin "28") (pinfunction "OSCO_28") (pintype "output"))
    )
    (net (code "56") (name "unconnected-(U2-~{CTS}-Pad8)") (class "Default")
      (node (ref "U2") (pin "8") (pinfunction "~{CTS}_8") (pintype "input"))
    )
    (net (code "57") (name "unconnected-(U2-~{DCD}-Pad7)") (class "Default")
      (node (ref "U2") (pin "7") (pinfunction "~{DCD}_7") (pintype "input"))
    )
    (net (code "58") (name "unconnected-(U2-~{DSR}-Pad6)") (class "Default")
      (node (ref "U2") (pin "6") (pinfunction "~{DSR}_6") (pintype "input"))
    )
    (net (code "59") (name "unconnected-(U2-~{RESET}-Pad18)") (class "Default")
      (node (ref "U2") (pin "18") (pinfunction "~{RESET}_18") (pintype "input"))
    )
    (net (code "60") (name "unconnected-(U2-~{RI}-Pad3)") (class "Default")
      (node (ref "U2") (pin "3") (pinfunction "~{RI}_3") (pintype "input"))
    )
  )
)
